# 5_pin_Motor_Control_Board.net
KiCad netlist of a schematic drawn in EAGLE
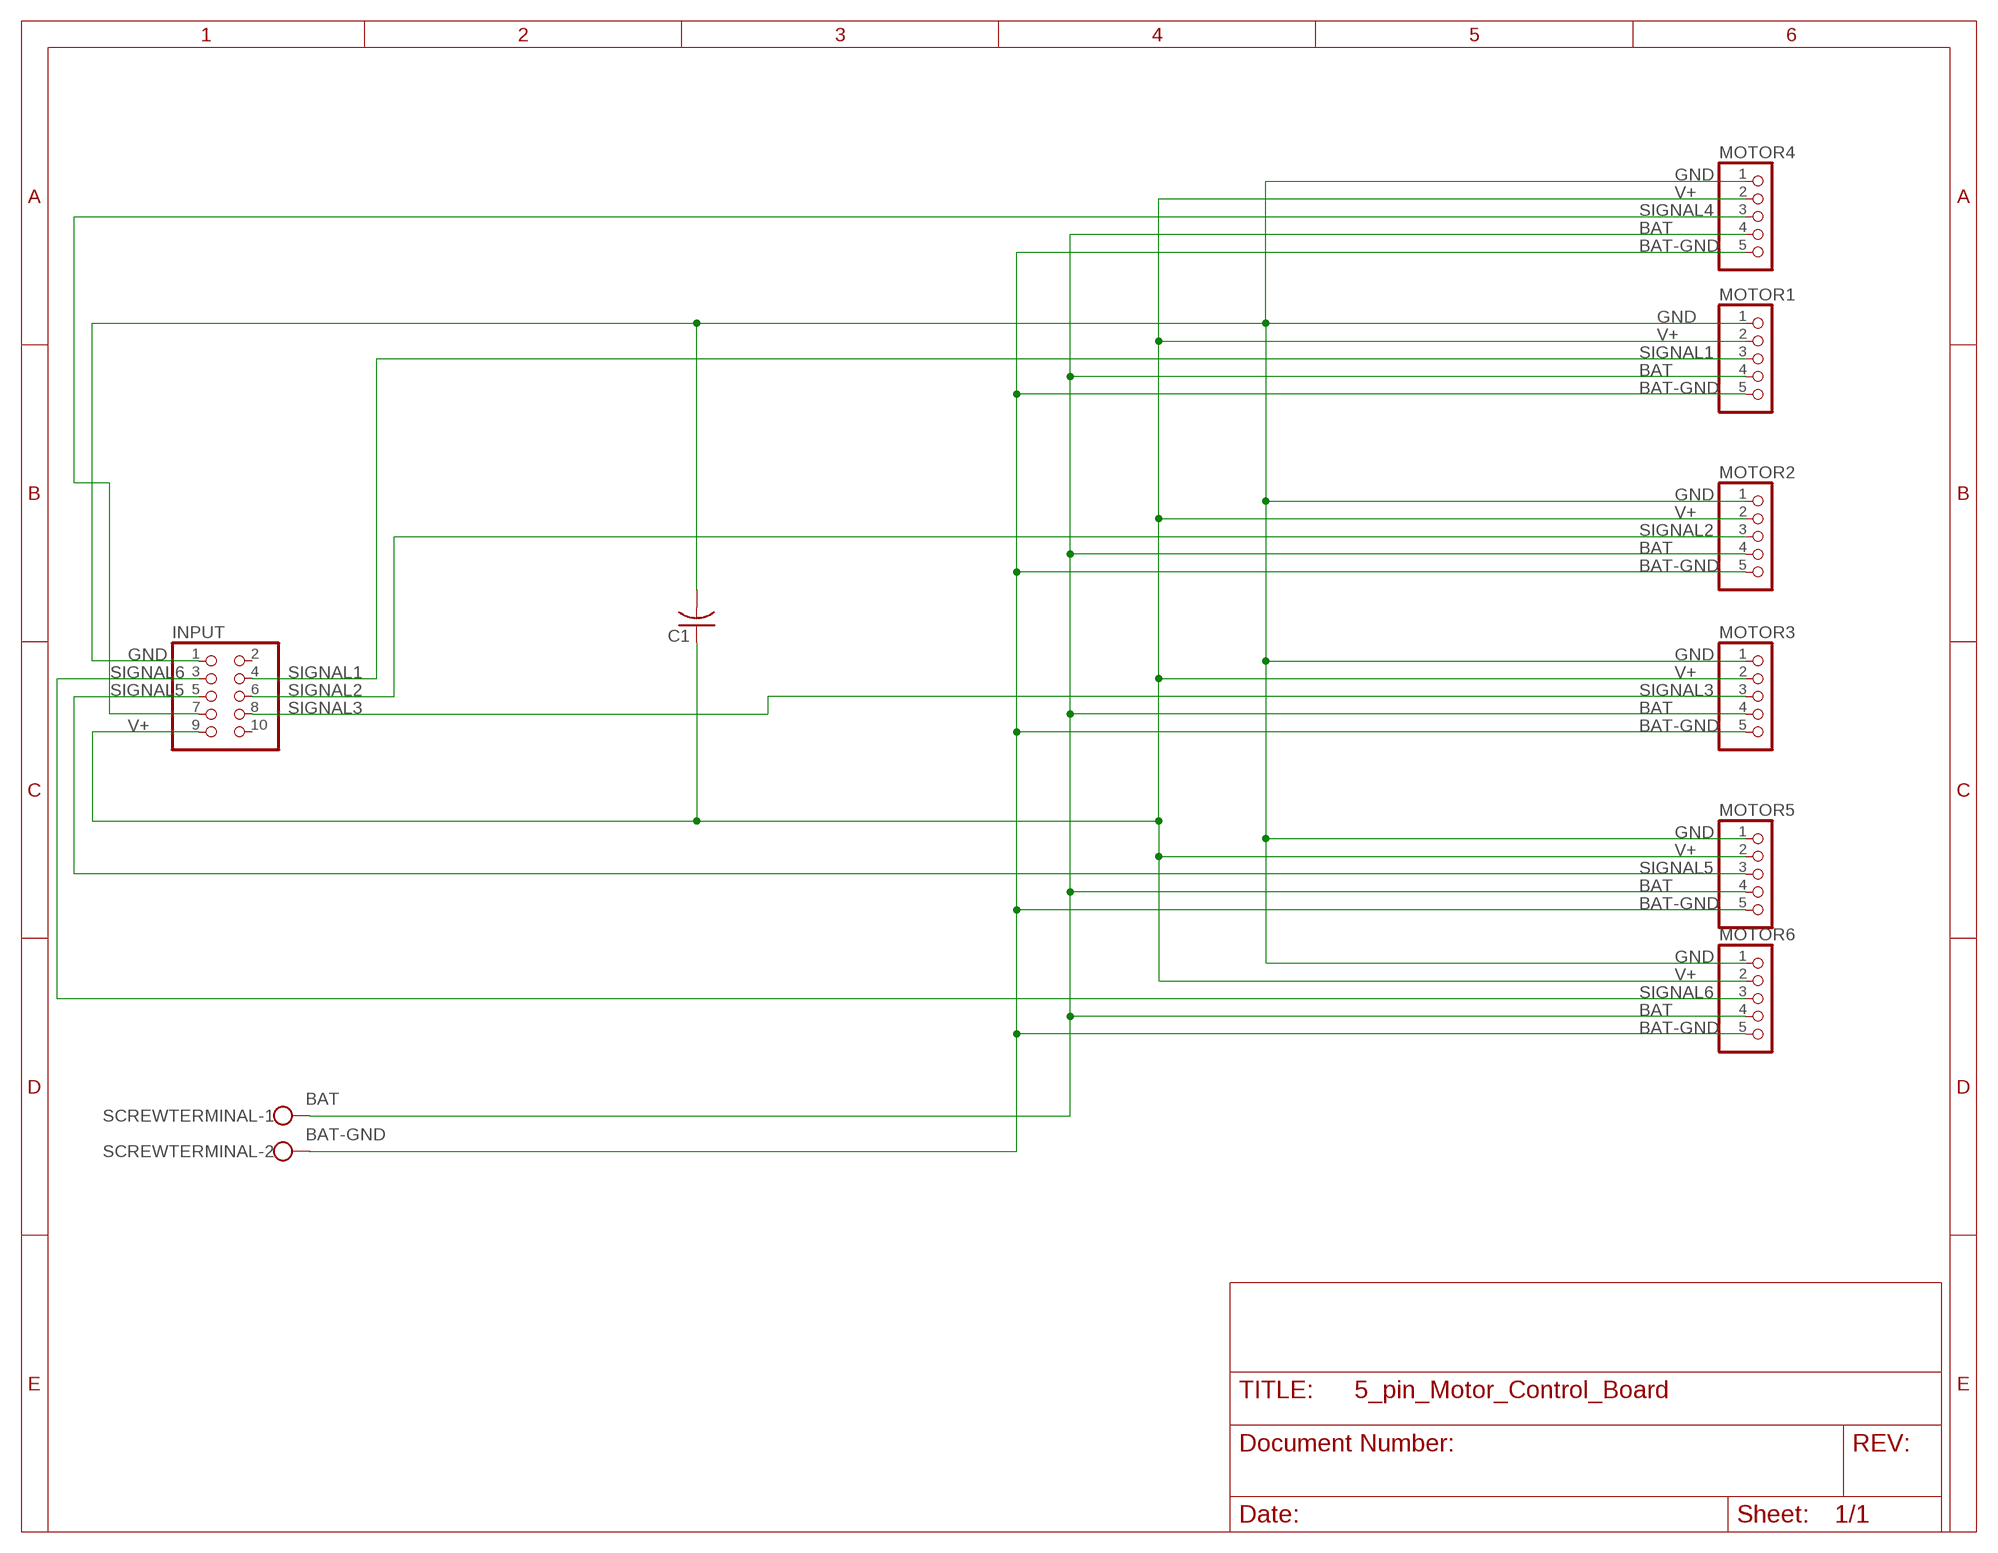
[diagram p0: schematic, sheet 1]

(export (version "E")
  (design (tool "Eeschema 10.0.6"))
  (components
    (comp (ref "C1")
      (value "C-US025-025X050")
      (footprint "eagle-import:C025-025X050")
      (libsource (lib "eagle-import") (part "C-US025-025X050"))
    )
    (comp (ref "INPUT")
      (value "PINHD-2X5")
      (footprint "eagle-import:2X05")
      (libsource (lib "eagle-import") (part "PINHD-2X5"))
    )
    (comp (ref "MOTOR1")
      (value "PINHD-1X5")
      (footprint "eagle-import:1X05")
      (libsource (lib "eagle-import") (part "PINHD-1X5"))
    )
    (comp (ref "MOTOR2")
      (value "PINHD-1X5")
      (footprint "eagle-import:1X05")
      (libsource (lib "eagle-import") (part "PINHD-1X5"))
    )
    (comp (ref "MOTOR3")
      (value "PINHD-1X5")
      (footprint "eagle-import:1X05")
      (libsource (lib "eagle-import") (part "PINHD-1X5"))
    )
    (comp (ref "MOTOR4")
      (value "PINHD-1X5")
      (footprint "eagle-import:1X05")
      (libsource (lib "eagle-import") (part "PINHD-1X5"))
    )
    (comp (ref "MOTOR5")
      (value "PINHD-1X5")
      (footprint "eagle-import:1X05")
      (libsource (lib "eagle-import") (part "PINHD-1X5"))
    )
    (comp (ref "MOTOR6")
      (value "PINHD-1X5")
      (footprint "eagle-import:1X05")
      (libsource (lib "eagle-import") (part "PINHD-1X5"))
    )
    (comp (ref "SCREWTERMINAL")
      (value "W237-102")
      (footprint "eagle-import:W237-102")
      (fields (field (name "MPN") "237-102"))
      (libsource (lib "eagle-import") (part "W237-102"))
    )
  )
  (nets
    (net (code "1") (name "/BAT") (class "Default")
      (node (ref "MOTOR1") (pin "4") (pinfunction "4_4") (pintype "passive"))
      (node (ref "MOTOR2") (pin "4") (pinfunction "4_4") (pintype "passive"))
      (node (ref "MOTOR3") (pin "4") (pinfunction "4_4") (pintype "passive"))
      (node (ref "MOTOR4") (pin "4") (pinfunction "4_4") (pintype "passive"))
      (node (ref "MOTOR5") (pin "4") (pinfunction "4_4") (pintype "passive"))
      (node (ref "MOTOR6") (pin "4") (pinfunction "4_4") (pintype "passive"))
      (node (ref "SCREWTERMINAL") (pin "1") (pinfunction "KL_1") (pintype "passive"))
    )
    (net (code "2") (name "/BAT-GND") (class "Default")
      (node (ref "MOTOR1") (pin "5") (pinfunction "5_5") (pintype "passive"))
      (node (ref "MOTOR2") (pin "5") (pinfunction "5_5") (pintype "passive"))
      (node (ref "MOTOR3") (pin "5") (pinfunction "5_5") (pintype "passive"))
      (node (ref "MOTOR4") (pin "5") (pinfunction "5_5") (pintype "passive"))
      (node (ref "MOTOR5") (pin "5") (pinfunction "5_5") (pintype "passive"))
      (node (ref "MOTOR6") (pin "5") (pinfunction "5_5") (pintype "passive"))
      (node (ref "SCREWTERMINAL") (pin "2") (pinfunction "KL_2") (pintype "passive"))
    )
    (net (code "3") (name "/GND") (class "Default")
      (node (ref "C1") (pin "2") (pinfunction "2_2") (pintype "passive"))
      (node (ref "INPUT") (pin "1") (pinfunction "1_1") (pintype "passive"))
      (node (ref "MOTOR1") (pin "1") (pinfunction "1_1") (pintype "passive"))
      (node (ref "MOTOR2") (pin "1") (pinfunction "1_1") (pintype "passive"))
      (node (ref "MOTOR3") (pin "1") (pinfunction "1_1") (pintype "passive"))
      (node (ref "MOTOR4") (pin "1") (pinfunction "1_1") (pintype "passive"))
      (node (ref "MOTOR5") (pin "1") (pinfunction "1_1") (pintype "passive"))
      (node (ref "MOTOR6") (pin "1") (pinfunction "1_1") (pintype "passive"))
    )
    (net (code "4") (name "/SIGNAL1") (class "Default")
      (node (ref "INPUT") (pin "4") (pinfunction "4_4") (pintype "passive"))
      (node (ref "MOTOR1") (pin "3") (pinfunction "3_3") (pintype "passive"))
    )
    (net (code "5") (name "/SIGNAL2") (class "Default")
      (node (ref "INPUT") (pin "6") (pinfunction "6_6") (pintype "passive"))
      (node (ref "MOTOR2") (pin "3") (pinfunction "3_3") (pintype "passive"))
    )
    (net (code "6") (name "/SIGNAL3") (class "Default")
      (node (ref "INPUT") (pin "8") (pinfunction "8_8") (pintype "passive"))
      (node (ref "MOTOR3") (pin "3") (pinfunction "3_3") (pintype "passive"))
    )
    (net (code "7") (name "/SIGNAL4") (class "Default")
      (node (ref "INPUT") (pin "7") (pinfunction "7_7") (pintype "passive"))
      (node (ref "MOTOR4") (pin "3") (pinfunction "3_3") (pintype "passive"))
    )
    (net (code "8") (name "/SIGNAL5") (class "Default")
      (node (ref "INPUT") (pin "5") (pinfunction "5_5") (pintype "passive"))
      (node (ref "MOTOR5") (pin "3") (pinfunction "3_3") (pintype "passive"))
    )
    (net (code "9") (name "/SIGNAL6") (class "Default")
      (node (ref "INPUT") (pin "3") (pinfunction "3_3") (pintype "passive"))
      (node (ref "MOTOR6") (pin "3") (pinfunction "3_3") (pintype "passive"))
    )
    (net (code "10") (name "/V+") (class "Default")
      (node (ref "C1") (pin "1") (pinfunction "1_1") (pintype "passive"))
      (node (ref "INPUT") (pin "9") (pinfunction "9_9") (pintype "passive"))
      (node (ref "MOTOR1") (pin "2") (pinfunction "2_2") (pintype "passive"))
      (node (ref "MOTOR2") (pin "2") (pinfunction "2_2") (pintype "passive"))
      (node (ref "MOTOR3") (pin "2") (pinfunction "2_2") (pintype "passive"))
      (node (ref "MOTOR4") (pin "2") (pinfunction "2_2") (pintype "passive"))
      (node (ref "MOTOR5") (pin "2") (pinfunction "2_2") (pintype "passive"))
      (node (ref "MOTOR6") (pin "2") (pinfunction "2_2") (pintype "passive"))
    )
    (net (code "11") (name "unconnected-(INPUT-Pad2)") (class "Default")
      (node (ref "INPUT") (pin "2") (pinfunction "2_2") (pintype "passive"))
    )
    (net (code "12") (name "unconnected-(INPUT-Pad10)") (class "Default")
      (node (ref "INPUT") (pin "10") (pinfunction "10_10") (pintype "passive"))
    )
  )
)
